# 2x3Keyboard.net
KiCad netlist of a schematic drawn in EAGLE
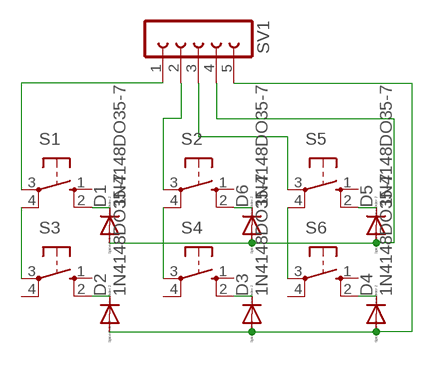
[diagram p0: schematic, sheet 1]

(export (version "E")
  (design (tool "Eeschema 10.0.6"))
  (components
    (comp (ref "D1")
      (value "1N4148DO35-7")
      (footprint "eagle-import:DO35-7")
      (libsource (lib "eagle-import") (part "1N4148DO35-7"))
    )
    (comp (ref "D2")
      (value "1N4148DO35-7")
      (footprint "eagle-import:DO35-7")
      (libsource (lib "eagle-import") (part "1N4148DO35-7"))
    )
    (comp (ref "D3")
      (value "1N4148DO35-7")
      (footprint "eagle-import:DO35-7")
      (libsource (lib "eagle-import") (part "1N4148DO35-7"))
    )
    (comp (ref "D4")
      (value "1N4148DO35-7")
      (footprint "eagle-import:DO35-7")
      (libsource (lib "eagle-import") (part "1N4148DO35-7"))
    )
    (comp (ref "D5")
      (value "1N4148DO35-7")
      (footprint "eagle-import:DO35-7")
      (libsource (lib "eagle-import") (part "1N4148DO35-7"))
    )
    (comp (ref "D6")
      (value "1N4148DO35-7")
      (footprint "eagle-import:DO35-7")
      (libsource (lib "eagle-import") (part "1N4148DO35-7"))
    )
    (comp (ref "S1")
      (value "10-XX")
      (footprint "eagle-import:B3F-10XX")
      (fields (field (name "MPN") "B3F-1000"))
      (libsource (lib "eagle-import") (part "10-XX"))
    )
    (comp (ref "S2")
      (value "10-XX")
      (footprint "eagle-import:B3F-10XX")
      (fields (field (name "MPN") "B3F-1000"))
      (libsource (lib "eagle-import") (part "10-XX"))
    )
    (comp (ref "S3")
      (value "10-XX")
      (footprint "eagle-import:B3F-10XX")
      (fields (field (name "MPN") "B3F-1000"))
      (libsource (lib "eagle-import") (part "10-XX"))
    )
    (comp (ref "S4")
      (value "10-XX")
      (footprint "eagle-import:B3F-10XX")
      (fields (field (name "MPN") "B3F-1000"))
      (libsource (lib "eagle-import") (part "10-XX"))
    )
    (comp (ref "S5")
      (value "10-XX")
      (footprint "eagle-import:B3F-10XX")
      (fields (field (name "MPN") "B3F-1000"))
      (libsource (lib "eagle-import") (part "10-XX"))
    )
    (comp (ref "S6")
      (value "10-XX")
      (footprint "eagle-import:B3F-10XX")
      (fields (field (name "MPN") "B3F-1000"))
      (libsource (lib "eagle-import") (part "10-XX"))
    )
    (comp (ref "SV1")
      (value "FE05-1")
      (footprint "eagle-import:FE05-1")
      (libsource (lib "eagle-import") (part "FE05-1"))
    )
  )
  (nets
    (net (code "1") (name "Net-(D1-PadA)") (class "Default")
      (node (ref "D1") (pin "A") (pinfunction "A_A") (pintype "passive"))
      (node (ref "D5") (pin "A") (pinfunction "A_A") (pintype "passive"))
      (node (ref "D6") (pin "A") (pinfunction "A_A") (pintype "passive"))
      (node (ref "SV1") (pin "4") (pinfunction "4_4") (pintype "passive"))
    )
    (net (code "2") (name "Net-(D2-PadA)") (class "Default")
      (node (ref "D2") (pin "A") (pinfunction "A_A") (pintype "passive"))
      (node (ref "D3") (pin "A") (pinfunction "A_A") (pintype "passive"))
      (node (ref "D4") (pin "A") (pinfunction "A_A") (pintype "passive"))
      (node (ref "SV1") (pin "5") (pinfunction "5_5") (pintype "passive"))
    )
    (net (code "3") (name "Net-(S1-P)") (class "Default")
      (node (ref "S1") (pin "3") (pinfunction "P_3") (pintype "passive"))
      (node (ref "SV1") (pin "1") (pinfunction "1_1") (pintype "passive"))
    )
    (net (code "4") (name "Net-(S1-P1)") (class "Default")
      (node (ref "S1") (pin "4") (pinfunction "P1_4") (pintype "passive"))
      (node (ref "S3") (pin "3") (pinfunction "P_3") (pintype "passive"))
    )
    (net (code "5") (name "Net-(S1-S1)") (class "Default")
      (node (ref "D1") (pin "C") (pinfunction "C_C") (pintype "passive"))
      (node (ref "S1") (pin "2") (pinfunction "S1_2") (pintype "passive"))
    )
    (net (code "6") (name "Net-(S2-P)") (class "Default")
      (node (ref "S2") (pin "3") (pinfunction "P_3") (pintype "passive"))
      (node (ref "SV1") (pin "2") (pinfunction "2_2") (pintype "passive"))
    )
    (net (code "7") (name "Net-(S2-P1)") (class "Default")
      (node (ref "S2") (pin "4") (pinfunction "P1_4") (pintype "passive"))
      (node (ref "S4") (pin "3") (pinfunction "P_3") (pintype "passive"))
    )
    (net (code "8") (name "Net-(S2-S1)") (class "Default")
      (node (ref "D6") (pin "C") (pinfunction "C_C") (pintype "passive"))
      (node (ref "S2") (pin "2") (pinfunction "S1_2") (pintype "passive"))
    )
    (net (code "9") (name "Net-(S3-S1)") (class "Default")
      (node (ref "D2") (pin "C") (pinfunction "C_C") (pintype "passive"))
      (node (ref "S3") (pin "2") (pinfunction "S1_2") (pintype "passive"))
    )
    (net (code "10") (name "Net-(S4-S1)") (class "Default")
      (node (ref "D3") (pin "C") (pinfunction "C_C") (pintype "passive"))
      (node (ref "S4") (pin "2") (pinfunction "S1_2") (pintype "passive"))
    )
    (net (code "11") (name "Net-(S5-P)") (class "Default")
      (node (ref "S5") (pin "3") (pinfunction "P_3") (pintype "passive"))
      (node (ref "SV1") (pin "3") (pinfunction "3_3") (pintype "passive"))
    )
    (net (code "12") (name "Net-(S5-P1)") (class "Default")
      (node (ref "S5") (pin "4") (pinfunction "P1_4") (pintype "passive"))
      (node (ref "S6") (pin "3") (pinfunction "P_3") (pintype "passive"))
    )
    (net (code "13") (name "Net-(S5-S1)") (class "Default")
      (node (ref "D5") (pin "C") (pinfunction "C_C") (pintype "passive"))
      (node (ref "S5") (pin "2") (pinfunction "S1_2") (pintype "passive"))
    )
    (net (code "14") (name "Net-(S6-S1)") (class "Default")
      (node (ref "D4") (pin "C") (pinfunction "C_C") (pintype "passive"))
      (node (ref "S6") (pin "2") (pinfunction "S1_2") (pintype "passive"))
    )
    (net (code "15") (name "unconnected-(S1-S-Pad1)") (class "Default")
      (node (ref "S1") (pin "1") (pinfunction "S_1") (pintype "passive"))
    )
    (net (code "16") (name "unconnected-(S2-S-Pad1)") (class "Default")
      (node (ref "S2") (pin "1") (pinfunction "S_1") (pintype "passive"))
    )
    (net (code "17") (name "unconnected-(S3-P1-Pad4)") (class "Default")
      (node (ref "S3") (pin "4") (pinfunction "P1_4") (pintype "passive"))
    )
    (net (code "18") (name "unconnected-(S3-S-Pad1)") (class "Default")
      (node (ref "S3") (pin "1") (pinfunction "S_1") (pintype "passive"))
    )
    (net (code "19") (name "unconnected-(S4-P1-Pad4)") (class "Default")
      (node (ref "S4") (pin "4") (pinfunction "P1_4") (pintype "passive"))
    )
    (net (code "20") (name "unconnected-(S4-S-Pad1)") (class "Default")
      (node (ref "S4") (pin "1") (pinfunction "S_1") (pintype "passive"))
    )
    (net (code "21") (name "unconnected-(S5-S-Pad1)") (class "Default")
      (node (ref "S5") (pin "1") (pinfunction "S_1") (pintype "passive"))
    )
    (net (code "22") (name "unconnected-(S6-P1-Pad4)") (class "Default")
      (node (ref "S6") (pin "4") (pinfunction "P1_4") (pintype "passive"))
    )
    (net (code "23") (name "unconnected-(S6-S-Pad1)") (class "Default")
      (node (ref "S6") (pin "1") (pinfunction "S_1") (pintype "passive"))
    )
  )
)
